# BMS_Rocket.net
KiCad netlist of a schematic drawn in Altium Designer
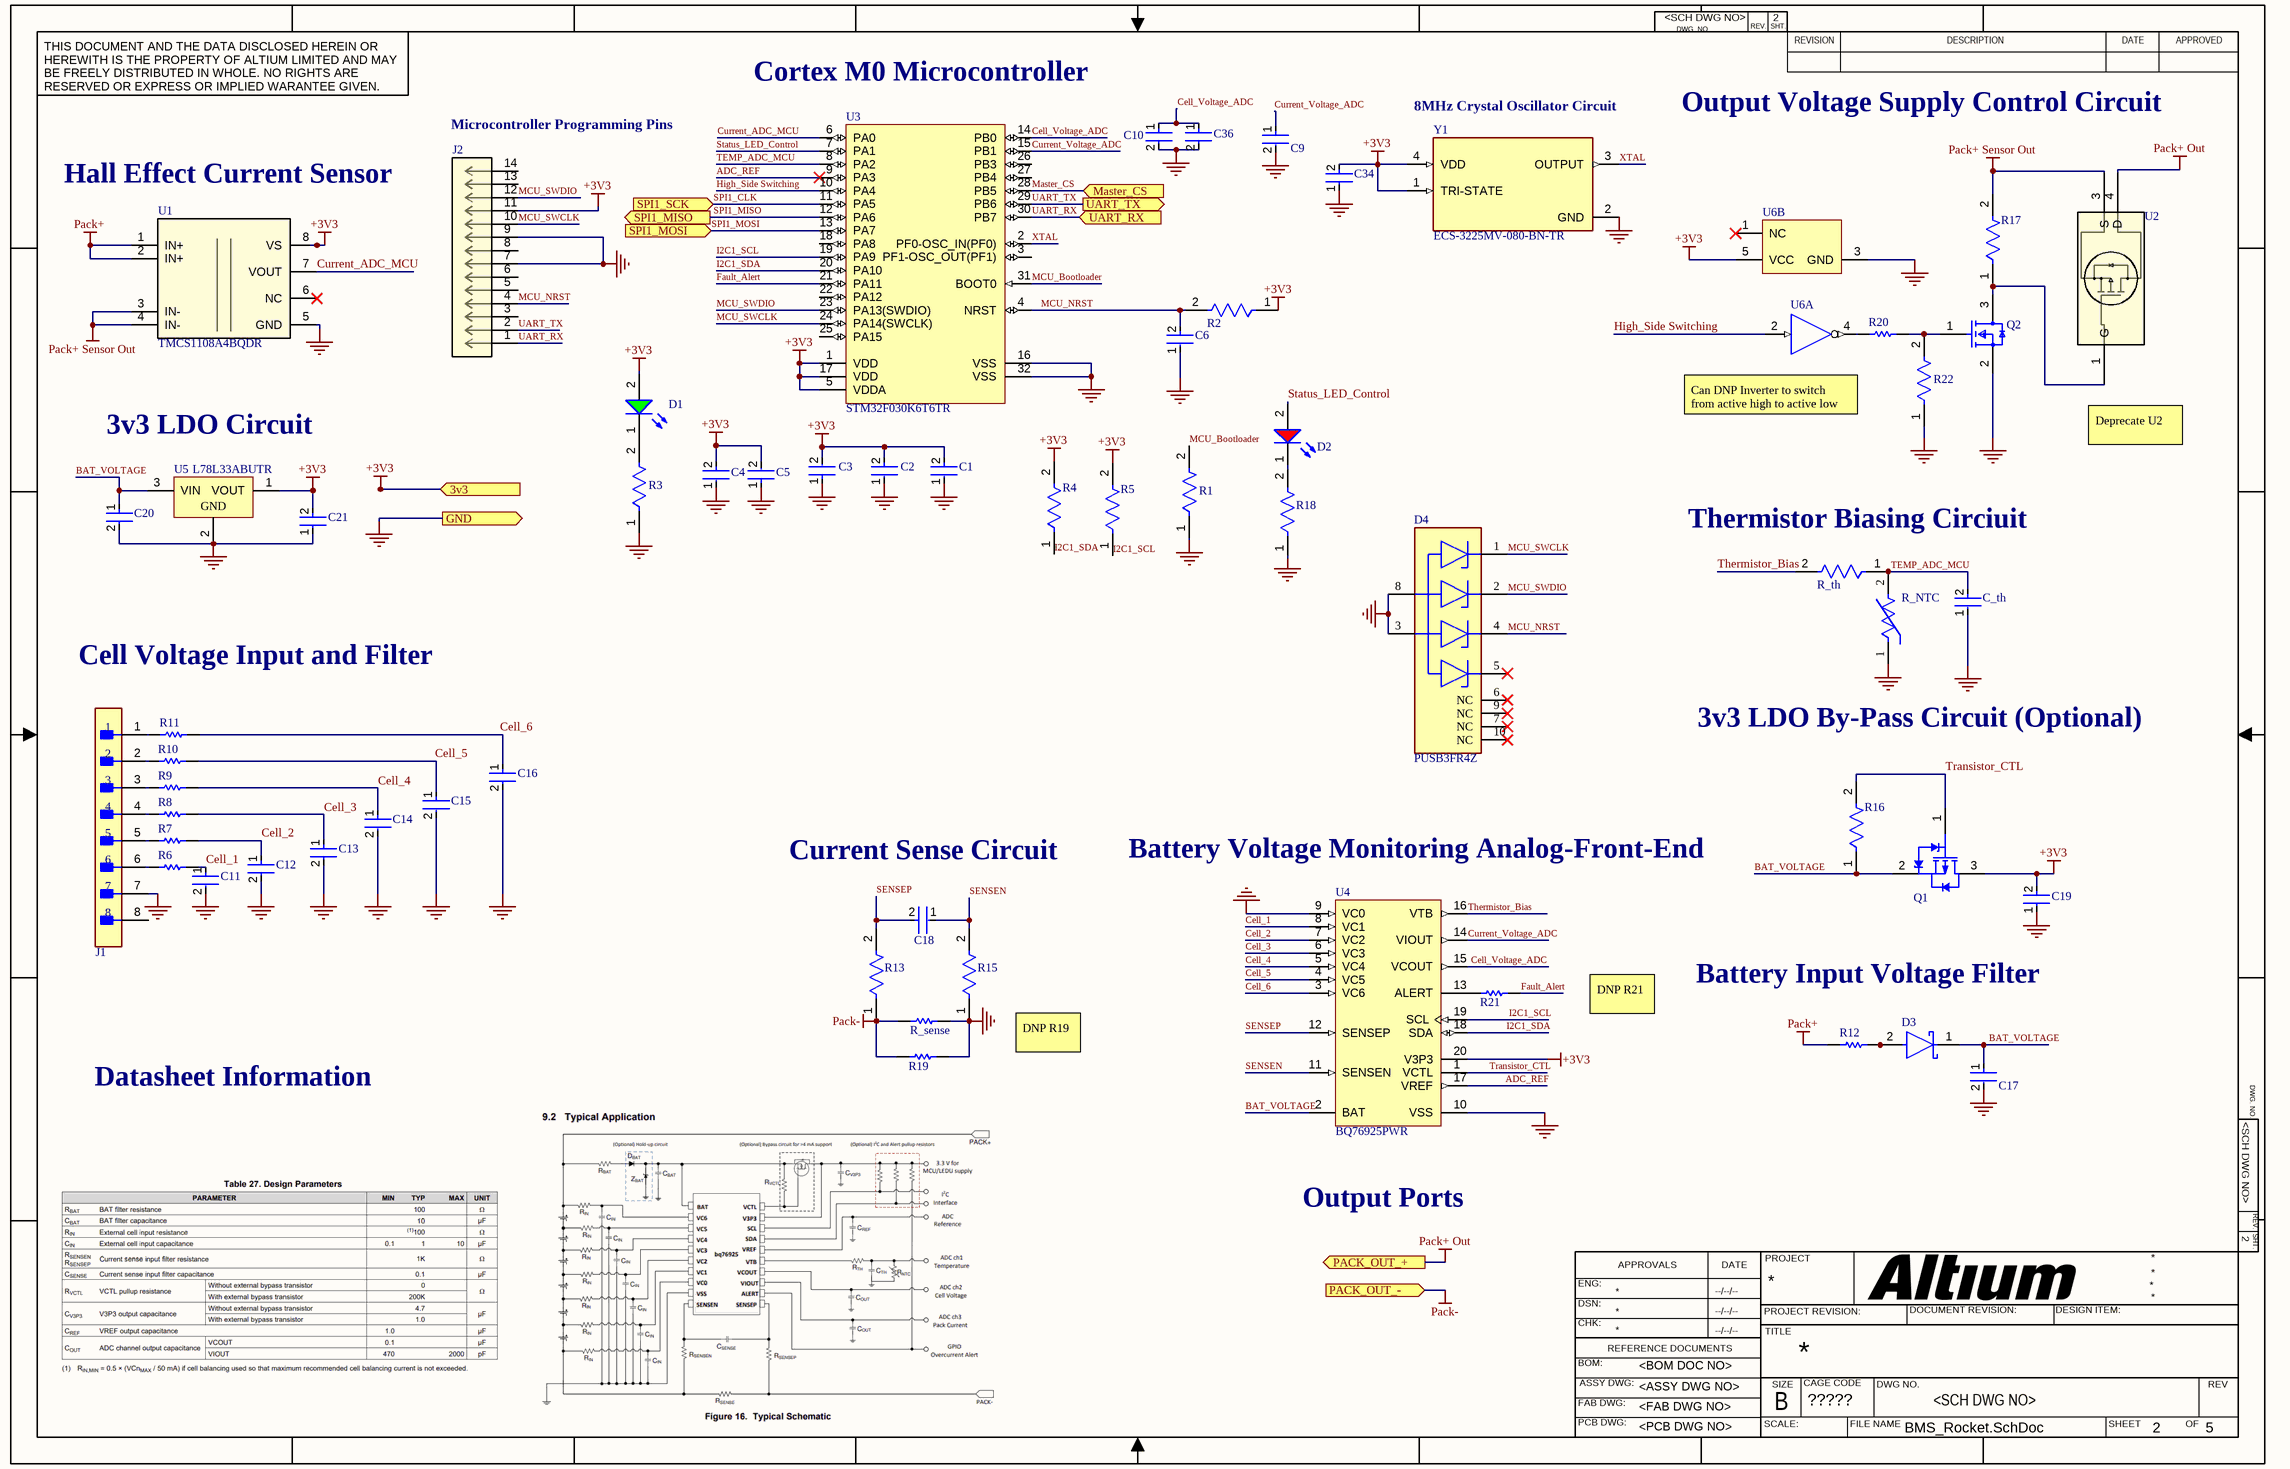
[diagram p0: BMS_Rocket.SchDoc]

(export (version "E")
  (design (tool "Eeschema 10.0.6"))
  (components
    (comp (ref "C1")
      (value "GRM155R71C104KA88D")
      (footprint "FP-GRM15-MFG")
      (description "CAP CER 0.1UF 16V X7R 0402")
      (fields
        (field (name "TOLERANCE") "10%")
        (field (name "OCTOPART") "https://octopart.com/grm155r71c104ka88d-murata-196880")
      )
      (libsource (lib "Altium Content Vault") (part "236180d848d6139a670b325ea6854c9"))
    )
    (comp (ref "C2")
      (value "GRM155R71C104KA88D")
      (footprint "FP-GRM15-MFG")
      (description "CAP CER 0.1UF 16V X7R 0402")
      (fields
        (field (name "TOLERANCE") "10%")
        (field (name "OCTOPART") "https://octopart.com/grm155r71c104ka88d-murata-196880")
      )
      (libsource (lib "Altium Content Vault") (part "236180d848d6139a670b325ea6854c9"))
    )
    (comp (ref "C3")
      (value "GRM188R6YA475KE15D")
      (footprint "FP-GRM188-0_2-IPC_C")
      (description "Chip Multilayer Ceramic Capacitors for General Purpose, 0603, 4.7uF, X5R, 15%, 10%, 35V")
      (fields (field (name "VOLTAGE") "35V") (field (name "TOLERANCE") "10%"))
      (libsource (lib "Altium Content Vault") (part "11868f565c42a9108669ba33697ecf6"))
    )
    (comp (ref "C4")
      (value "C1608X5R1H105K080AB")
      (footprint "FP-C1608-080-0_1-IPC_B")
      (description "Multilayer Ceramic Capacitors 1μF ±10% 50V X5R SMD 0603")
      (fields (field (name "VOLTAGE") "50V") (field (name "TOLERANCE") "10%"))
      (libsource (lib "Altium Content Vault") (part "236180d848d6139a670b325ea6854c9"))
    )
    (comp (ref "C5")
      (value "CC0603KRX7R9BB103")
      (footprint "FP-CC0603-DA-MFG")
      (description "CAP CER 10000PF 50V X7R 0603")
      (fields (field (name "TOLERANCE") "0.1") (field (name "MANUFACTURER") "YAGEO"))
      (libsource (lib "Altium Content Vault") (part "11868f565c42a9108669ba33697ecf6"))
    )
    (comp (ref "C6")
      (value "GRM155R71C104KA88D")
      (footprint "FP-GRM15-MFG")
      (description "CAP CER 0.1UF 16V X7R 0402")
      (fields
        (field (name "TOLERANCE") "10%")
        (field (name "OCTOPART") "https://octopart.com/grm155r71c104ka88d-murata-196880")
      )
      (libsource (lib "Altium Content Vault") (part "236180d848d6139a670b325ea6854c9"))
    )
    (comp (ref "C9")
      (value "GRM1885C1H202JA01D")
      (footprint "FP-GRM188-0_1-e0_2_0_5-IPC_B")
      (description "Chip Multilayer Ceramic Capacitors for General Purpose, 0603, 2000pF, C0G, 30ppm/°C, 5%, 50V")
      (fields (field (name "TOLERANCE") "5%") (field (name "VOLTAGE") "50V"))
      (libsource (lib "Altium Content Vault") (part "11868f565c42a9108669ba33697ecf6"))
    )
    (comp (ref "C10")
      (value "CC0402KRX7R8BB102")
      (footprint "FP-CC0402-MFG")
      (description "CAP CER 1000PF 25V X7R 0402")
      (fields
        (field (name "MANUFACTURER") "YAGEO")
        (field (name "OCTOPART") "https://octopart.com/cc0402krx7r8bb102-yageo-12885104")
      )
      (libsource (lib "Altium Content Vault") (part "11868f565c42a9108669ba33697ecf6"))
    )
    (comp (ref "C11")
      (value "UMK107AB7105KA-T")
      (footprint "FP-0603-L_1_6_0_15-W_0_8-IPC_C")
      (description "Ceramic Capacitor General Use 1uF ±10% 50V X7R 0603")
      (fields (field (name "TOLERANCE") "10%"))
      (libsource (lib "Altium Content Vault") (part "11868f565c42a9108669ba33697ecf6"))
    )
    (comp (ref "C12")
      (value "UMK107AB7105KA-T")
      (footprint "FP-0603-L_1_6_0_15-W_0_8-IPC_C")
      (description "Ceramic Capacitor General Use 1uF ±10% 50V X7R 0603")
      (fields (field (name "TOLERANCE") "10%"))
      (libsource (lib "Altium Content Vault") (part "11868f565c42a9108669ba33697ecf6"))
    )
    (comp (ref "C13")
      (value "UMK107AB7105KA-T")
      (footprint "FP-0603-L_1_6_0_15-W_0_8-IPC_C")
      (description "Ceramic Capacitor General Use 1uF ±10% 50V X7R 0603")
      (fields (field (name "TOLERANCE") "10%"))
      (libsource (lib "Altium Content Vault") (part "11868f565c42a9108669ba33697ecf6"))
    )
    (comp (ref "C14")
      (value "UMK107AB7105KA-T")
      (footprint "FP-0603-L_1_6_0_15-W_0_8-IPC_C")
      (description "Ceramic Capacitor General Use 1uF ±10% 50V X7R 0603")
      (fields (field (name "TOLERANCE") "10%"))
      (libsource (lib "Altium Content Vault") (part "11868f565c42a9108669ba33697ecf6"))
    )
    (comp (ref "C15")
      (value "UMK107AB7105KA-T")
      (footprint "FP-0603-L_1_6_0_15-W_0_8-IPC_C")
      (description "Ceramic Capacitor General Use 1uF ±10% 50V X7R 0603")
      (fields (field (name "TOLERANCE") "10%"))
      (libsource (lib "Altium Content Vault") (part "11868f565c42a9108669ba33697ecf6"))
    )
    (comp (ref "C16")
      (value "UMK107AB7105KA-T")
      (footprint "FP-0603-L_1_6_0_15-W_0_8-IPC_C")
      (description "Ceramic Capacitor General Use 1uF ±10% 50V X7R 0603")
      (fields (field (name "TOLERANCE") "10%"))
      (libsource (lib "Altium Content Vault") (part "11868f565c42a9108669ba33697ecf6"))
    )
    (comp (ref "C17")
      (value "C3216X5R1H106M160AB")
      (footprint "FP-C3216-160-0_2-MFG")
      (description "Multilayer Ceramic Capacitors 10uF ±20% 50V X5R SMD 1206")
      (fields (field (name "TOLERANCE") "20%"))
      (libsource (lib "Altium Content Vault") (part "11868f565c42a9108669ba33697ecf6"))
    )
    (comp (ref "C18")
      (value "GRM155R71C104KA88D")
      (footprint "FP-GRM15-MFG")
      (description "CAP CER 0.1UF 16V X7R 0402")
      (fields
        (field (name "TOLERANCE") "10%")
        (field (name "OCTOPART") "https://octopart.com/grm155r71c104ka88d-murata-196880")
      )
      (libsource (lib "Altium Content Vault") (part "236180d848d6139a670b325ea6854c9"))
    )
    (comp (ref "C19")
      (value "C1608X5R1H105K080AB")
      (footprint "FP-C1608-080-0_1-IPC_B")
      (description "Multilayer Ceramic Capacitors 1μF ±10% 50V X5R SMD 0603")
      (fields (field (name "VOLTAGE") "50V") (field (name "TOLERANCE") "10%"))
      (libsource (lib "Altium Content Vault") (part "236180d848d6139a670b325ea6854c9"))
    )
    (comp (ref "C20")
      (value "CGA3E3X7R1H334K080AB")
      (footprint "FP-CGA3E-0_3-0_1-IPC_B")
      (description "Cap Ceramic 330nF 50V X7R 10% Pad SMD 0603 +125°C Automotive T/R")
      (fields (field (name "TOLERANCE") "10%"))
      (libsource (lib "Altium Content Vault") (part "b4654b650e69147ec39a6b967a45e02"))
    )
    (comp (ref "C21")
      (value "GRM155R71C104KA88D")
      (footprint "FP-GRM15-MFG")
      (description "CAP CER 0.1UF 16V X7R 0402")
      (fields
        (field (name "TOLERANCE") "10%")
        (field (name "OCTOPART") "https://octopart.com/grm155r71c104ka88d-murata-196880")
      )
      (libsource (lib "Altium Content Vault") (part "236180d848d6139a670b325ea6854c9"))
    )
    (comp (ref "C34")
      (value "GRM155R71C104KA88D")
      (footprint "FP-GRM15-MFG")
      (description "CAP CER 0.1UF 16V X7R 0402")
      (fields
        (field (name "TOLERANCE") "10%")
        (field (name "OCTOPART") "https://octopart.com/grm155r71c104ka88d-murata-196880")
      )
      (libsource (lib "Altium Content Vault") (part "236180d848d6139a670b325ea6854c9"))
    )
    (comp (ref "C36")
      (value "CC0402KRX7R8BB102")
      (footprint "FP-CC0402-MFG")
      (description "CAP CER 1000PF 25V X7R 0402")
      (fields
        (field (name "MANUFACTURER") "YAGEO")
        (field (name "OCTOPART") "https://octopart.com/cc0402krx7r8bb102-yageo-12885104")
      )
      (libsource (lib "Altium Content Vault") (part "11868f565c42a9108669ba33697ecf6"))
    )
    (comp (ref "C_th")
      (value "GRM155R71C104KA88D")
      (footprint "FP-GRM15-MFG")
      (description "CAP CER 0.1UF 16V X7R 0402")
      (fields
        (field (name "TOLERANCE") "10%")
        (field (name "OCTOPART") "https://octopart.com/grm155r71c104ka88d-murata-196880")
      )
      (libsource (lib "Altium Content Vault") (part "236180d848d6139a670b325ea6854c9"))
    )
    (comp (ref "D1")
      (value "150060VS75000")
      (footprint "WL-SMCW_0603_150060xx75000")
      (description "WURTH ELEKTRONIK - 150060VS75000 - LED, Green, SMD, 0603, 30 mA, 2 V, 570 nm")
      (libsource (lib "Altium Content Vault") (part "LED_Green_2A-1K"))
    )
    (comp (ref "D2")
      (value "150060SS75000")
      (footprint "WL-SMCW_0603_150060xx75000")
      (description "Led, Red, 630 Nm, 1.9 V, 30 Ma, 60 Mcd Rohs Compliant: Yes")
      (libsource (lib "Altium Content Vault") (part "LED_Red_2A-1K"))
    )
    (comp (ref "D3")
      (value "B0520LW-7-F")
      (footprint "FP-SOD123-MFG")
      (description "DIODE SCHOTTKY 20V 500MA SOD123")
      (fields
        (field (name "OCTOPART") "https://octopart.com/b0520lw-7-f-diodes+inc.-325707")
        (field (name "MANUFACTURER") "Diodes Inc.")
      )
      (libsource (lib "Altium Content Vault") (part "1d6ec82d83fb6aee721767c19dac4b9"))
    )
    (comp (ref "D4")
      (value "PUSB3FR4Z")
      (footprint "FP-SOT1176-1-MFG")
      (description "TVS DIODE 3.3VWM 3VC DFN2510A-10")
      (libsource (lib "Altium Content Vault") (part "7af82cefb99888626757485c32e8fb9"))
    )
    (comp (ref "J1")
      (value "M20-9990846")
      (footprint "FP-M20-9990846-MFG")
      (description "CONN HEADER VERT 8POS 2.54MM")
      (libsource (lib "Altium Content Vault") (part "99ec2b232beb5d2356d4d77f6a047f0"))
    )
    (comp (ref "J2")
      (value "3220-14-0100-00")
      (footprint "CONN14_3220-14_CNC")
      (description "No Description Available")
      (libsource (lib "3220-14-0100-00") (part "3220-14-0100-00"))
    )
    (comp (ref "Q1")
      (value "BSS84AK,215")
      (footprint "NXP-SOT23_N")
      (description "P-Channel Trench MOSFET, -50 V, -0.18 A, -55 to 150 degC, 3-Pin SOT23, Tape and Reel")
      (fields (field (name "MANUFACTURER") "NXP Semiconductors"))
      (libsource (lib "Altium Content Vault") (part "NXP-PMOS-GSD-3_B"))
    )
    (comp (ref "Q2")
      (value "2N7002-7-F")
      (footprint "FP-SOT23-MFG")
      (description "MOSFET N-CH 60V 115MA SOT23-3")
      (fields (field (name "VOLTAGE") "60V"))
      (libsource (lib "Altium Content Vault") (part "3b9c635fedb024a5347a57b145af9cc"))
    )
    (comp (ref "R1")
      (value "RC0603FR-0710KL")
      (footprint "FP-RC0603-0_55-IPC_C")
      (description "RES 10K OHM 1% 1/10W 0603")
      (fields (field (name "TOLERANCE") "1%"))
      (libsource (lib "Altium Content Vault") (part "1029c3af85768c4190bb7ad29bc67b5"))
    )
    (comp (ref "R2")
      (value "RC0603FR-0710KL")
      (footprint "FP-RC0603-0_55-IPC_C")
      (description "RES 10K OHM 1% 1/10W 0603")
      (fields (field (name "TOLERANCE") "1%"))
      (libsource (lib "Altium Content Vault") (part "1029c3af85768c4190bb7ad29bc67b5"))
    )
    (comp (ref "R3")
      (value "RC0603FR-0710KL")
      (footprint "FP-RC0603-0_55-IPC_C")
      (description "RES 10K OHM 1% 1/10W 0603")
      (fields (field (name "TOLERANCE") "1%"))
      (libsource (lib "Altium Content Vault") (part "1029c3af85768c4190bb7ad29bc67b5"))
    )
    (comp (ref "R4")
      (value "CRCW06034K70FKEA")
      (footprint "FP-CRCW0603-e3-IPC_A")
      (description "RES Thick Film, 4.7kΩ, 1%, 0.1W, 100ppm/°C, 0603")
      (fields (field (name "TOLERANCE") "1%"))
      (libsource (lib "Altium Content Vault") (part "1029c3af85768c4190bb7ad29bc67b5"))
    )
    (comp (ref "R5")
      (value "CRCW06034K70FKEA")
      (footprint "FP-CRCW0603-e3-IPC_A")
      (description "RES Thick Film, 4.7kΩ, 1%, 0.1W, 100ppm/°C, 0603")
      (fields (field (name "TOLERANCE") "1%"))
      (libsource (lib "Altium Content Vault") (part "1029c3af85768c4190bb7ad29bc67b5"))
    )
    (comp (ref "R6")
      (value "CRCW0603100RFKEA")
      (footprint "RESC1609X50X30ML8T20")
      (description "Chip Resistor, 100 Ohm, +/- 1%, 100 mW,-55 to 155 degC, 0603 (1608 Metric), RoHS, Tape and Ree")
      (fields (field (name "MANUFACTURER") "Vishay Semiconductor"))
      (libsource (lib "Altium Content Vault") (part "RES-2"))
    )
    (comp (ref "R7")
      (value "CRCW0603100RFKEA")
      (footprint "RESC1609X50X30ML8T20")
      (description "Chip Resistor, 100 Ohm, +/- 1%, 100 mW,-55 to 155 degC, 0603 (1608 Metric), RoHS, Tape and Ree")
      (fields (field (name "MANUFACTURER") "Vishay Semiconductor"))
      (libsource (lib "Altium Content Vault") (part "RES-2"))
    )
    (comp (ref "R8")
      (value "CRCW0603100RFKEA")
      (footprint "RESC1609X50X30ML8T20")
      (description "Chip Resistor, 100 Ohm, +/- 1%, 100 mW,-55 to 155 degC, 0603 (1608 Metric), RoHS, Tape and Ree")
      (fields (field (name "MANUFACTURER") "Vishay Semiconductor"))
      (libsource (lib "Altium Content Vault") (part "RES-2"))
    )
    (comp (ref "R9")
      (value "CRCW0603100RFKEA")
      (footprint "RESC1609X50X30ML8T20")
      (description "Chip Resistor, 100 Ohm, +/- 1%, 100 mW,-55 to 155 degC, 0603 (1608 Metric), RoHS, Tape and Ree")
      (fields (field (name "MANUFACTURER") "Vishay Semiconductor"))
      (libsource (lib "Altium Content Vault") (part "RES-2"))
    )
    (comp (ref "R10")
      (value "CRCW0603100RFKEA")
      (footprint "RESC1609X50X30ML8T20")
      (description "Chip Resistor, 100 Ohm, +/- 1%, 100 mW,-55 to 155 degC, 0603 (1608 Metric), RoHS, Tape and Ree")
      (fields (field (name "MANUFACTURER") "Vishay Semiconductor"))
      (libsource (lib "Altium Content Vault") (part "RES-2"))
    )
    (comp (ref "R11")
      (value "CRCW0603100RFKEA")
      (footprint "RESC1609X50X30ML8T20")
      (description "Chip Resistor, 100 Ohm, +/- 1%, 100 mW,-55 to 155 degC, 0603 (1608 Metric), RoHS, Tape and Ree")
      (fields (field (name "MANUFACTURER") "Vishay Semiconductor"))
      (libsource (lib "Altium Content Vault") (part "RES-2"))
    )
    (comp (ref "R12")
      (value "RK73B1JTTD111J")
      (footprint "RESC1608X55X30NL20T10")
      (fields (field (name "MANUFACTURER") "KOA Speer"))
      (libsource (lib "Altium Content Vault") (part "RES"))
    )
    (comp (ref "R13")
      (value "AC0603FR-071KL")
      (footprint "FP-AC0603-IPC_B")
      (description "RES 1kΩ 1.00% 0.1W 0603")
      (fields (field (name "TOLERANCE") "1%"))
      (libsource (lib "Altium Content Vault") (part "1029c3af85768c4190bb7ad29bc67b5"))
    )
    (comp (ref "R15")
      (value "AC0603FR-071KL")
      (footprint "FP-AC0603-IPC_B")
      (description "RES 1kΩ 1.00% 0.1W 0603")
      (fields (field (name "TOLERANCE") "1%"))
      (libsource (lib "Altium Content Vault") (part "1029c3af85768c4190bb7ad29bc67b5"))
    )
    (comp (ref "R16")
      (value "CRCW0603200KFKEA")
      (footprint "FP-CRCW0603-e3-IPC_C")
      (description "RES Thick Film, 200kΩ, 1%, 0.1W, 100ppm/°C, 0603")
      (fields (field (name "TOLERANCE") "1%"))
      (libsource (lib "Altium Content Vault") (part "1029c3af85768c4190bb7ad29bc67b5"))
    )
    (comp (ref "R17")
      (value "CRCW0603200KFKEA")
      (footprint "FP-CRCW0603-e3-IPC_C")
      (description "RES Thick Film, 200kΩ, 1%, 0.1W, 100ppm/°C, 0603")
      (fields (field (name "TOLERANCE") "1%"))
      (libsource (lib "Altium Content Vault") (part "1029c3af85768c4190bb7ad29bc67b5"))
    )
    (comp (ref "R18")
      (value "RC0603FR-0710KL")
      (footprint "FP-RC0603-0_55-IPC_C")
      (description "RES 10K OHM 1% 1/10W 0603")
      (fields (field (name "TOLERANCE") "1%"))
      (libsource (lib "Altium Content Vault") (part "1029c3af85768c4190bb7ad29bc67b5"))
    )
    (comp (ref "R19")
      (value "RC0603JR-070RL")
      (footprint "RESC1608X55X25ML10T15")
      (description "Chip Resistor, 0 Ohm, +/- 5%, 0.1 W, -55 to 155 degC, 0603 (1608 Metric), RoHS, Tape and Reel")
      (fields (field (name "TOLERANCE") "5%") (field (name "MANUFACTURER") "Yageo"))
      (libsource (lib "Altium Content Vault") (part "RES-2"))
    )
    (comp (ref "R20")
      (value "RK73B1JTTD111J")
      (footprint "RESC1608X55X30NL20T10")
      (fields (field (name "MANUFACTURER") "KOA Speer"))
      (libsource (lib "Altium Content Vault") (part "RES"))
    )
    (comp (ref "R21")
      (value "RC0603JR-070RL")
      (footprint "RESC1608X55X25ML10T15")
      (description "Chip Resistor, 0 Ohm, +/- 5%, 0.1 W, -55 to 155 degC, 0603 (1608 Metric), RoHS, Tape and Reel")
      (fields (field (name "TOLERANCE") "5%") (field (name "MANUFACTURER") "Yageo"))
      (libsource (lib "Altium Content Vault") (part "RES-2"))
    )
    (comp (ref "R22")
      (value "RC0603FR-0710KL")
      (footprint "FP-RC0603-0_55-IPC_C")
      (description "RES 10K OHM 1% 1/10W 0603")
      (fields (field (name "TOLERANCE") "1%"))
      (libsource (lib "Altium Content Vault") (part "1029c3af85768c4190bb7ad29bc67b5"))
    )
    (comp (ref "R_NTC")
      (value "ERT-J1VG103FA")
      (footprint "FP-ERTJ1-MFG")
      (description "THERMISTOR NTC 10KOHM 3380K 0603")
      (fields (field (name "TOLERANCE") "1%"))
      (libsource (lib "Altium Content Vault") (part "3b148a6ebabc5fb4d708a66c052d352"))
    )
    (comp (ref "R_sense")
      (value "RL1220S-R15-F")
      (footprint "RESC2013X50X40LL20T20")
      (fields (field (name "MANUFACTURER") "Susumu"))
      (libsource (lib "Altium Content Vault") (part "RES"))
    )
    (comp (ref "R_th")
      (value "RC0603FR-0710KL")
      (footprint "FP-RC0603-0_55-IPC_C")
      (description "RES 10K OHM 1% 1/10W 0603")
      (fields (field (name "TOLERANCE") "1%"))
      (libsource (lib "Altium Content Vault") (part "1029c3af85768c4190bb7ad29bc67b5"))
    )
    (comp (ref "U1")
      (value "TMCS1108A4BQDR")
      (footprint "D0008A-IPC_A")
      (description "No Description Available")
      (libsource (lib "TMCS1108A4BQDR") (part "TMCS1108A4BQDR"))
    )
    (comp (ref "U2")
      (value "FQD11P06TM")
      (footprint "TO-252-3_ONS")
      (description "No Description Available")
      (libsource (lib "FQD11P06TM") (part "FQD11P06TM"))
    )
    (comp (ref "U3")
      (value "STM32F030K6T6TR")
      (footprint "STM-LQFP32_M")
      (fields (field (name "MANUFACTURER") "STMicroelectronics"))
      (libsource (lib "Altium Content Vault") (part "MC-ARM-STM32F030-LQFP32"))
    )
    (comp (ref "U4")
      (value "BQ76925PWR")
      (footprint "PW0020A_L")
      (fields (field (name "MANUFACTURER") "Texas Instruments"))
      (libsource (lib "Altium Content Vault") (part "TI-BQ76925PW20"))
    )
    (comp (ref "U5")
      (value "L78L33ABUTR")
      (footprint "SOT-89_N")
      (description "Positive Voltage Regulator, 3.3V, 4-Pin SOT-89, Tape and Reel")
      (libsource (lib "Altium Content Vault") (part "PM-REG-7805-SIL3"))
    )
    (comp (ref "U6")
      (value "SN74LVC1G04DCKR")
      (footprint "DCK0005A_N")
      (description "Single Inverter, DCK0005A, LARGE T&R")
      (fields
        (field (name "GENERIC PART NUMBER") "SN74LVC1G04")
        (field (name "MANUFACTURER") "Texas Instruments")
      )
      (libsource (lib "Altium Content Vault") (part "TI-SN74XXX1XX4-XX-5"))
    )
    (comp (ref "Y1")
      (value "ECS-3225MV-080-BN-TR")
      (footprint "OSC_ECS-3225MV-080-BN-TR")
      (description "8 MHz XO (Standard) HCMOS Oscillator 1.62V ~ 3.63V Enable/Disable 4-SMD, No Lead")
      (fields (field (name "MF") "ECS Inc."))
      (libsource (lib "ECS-3225MV-080-BN-TR") (part "ECS-3225MV-080-BN-TR"))
    )
  )
  (nets
    (net (code "1") (name "+3V3") (class "Default")
      (node (ref "C1") (pin "2") (pinfunction "2_2") (pintype "passive"))
      (node (ref "C19") (pin "2") (pinfunction "2_2") (pintype "passive"))
      (node (ref "C2") (pin "2") (pinfunction "2_2") (pintype "passive"))
      (node (ref "C21") (pin "2") (pinfunction "2_2") (pintype "passive"))
      (node (ref "C3") (pin "2") (pinfunction "2_2") (pintype "passive"))
      (node (ref "C34") (pin "2") (pinfunction "2_2") (pintype "passive"))
      (node (ref "C4") (pin "2") (pinfunction "2_2") (pintype "passive"))
      (node (ref "C5") (pin "2") (pinfunction "2_2") (pintype "passive"))
      (node (ref "D1") (pin "2") (pinfunction "A_2") (pintype "passive"))
      (node (ref "J2") (pin "11") (pinfunction "11_11") (pintype "passive"))
      (node (ref "Q1") (pin "3") (pinfunction "D_3") (pintype "passive"))
      (node (ref "R2") (pin "1") (pinfunction "1_1") (pintype "passive"))
      (node (ref "R4") (pin "2") (pinfunction "2_2") (pintype "passive"))
      (node (ref "R5") (pin "2") (pinfunction "2_2") (pintype "passive"))
      (node (ref "U1") (pin "8") (pinfunction "VS_8") (pintype "power_in"))
      (node (ref "U3") (pin "1") (pinfunction "VDD_1") (pintype "power_in"))
      (node (ref "U3") (pin "17") (pinfunction "VDD_17") (pintype "power_in"))
      (node (ref "U3") (pin "5") (pinfunction "VDDA_5") (pintype "power_in"))
      (node (ref "U4") (pin "20") (pinfunction "V3P3_20") (pintype "power_in"))
      (node (ref "U5") (pin "1") (pinfunction "VOUT_1") (pintype "power_in"))
      (node (ref "U6") (pin "5") (pinfunction "VCC_5") (pintype "power_in"))
      (node (ref "Y1") (pin "1") (pinfunction "TRI-STATE_1") (pintype "input"))
      (node (ref "Y1") (pin "4") (pinfunction "VDD_4") (pintype "input"))
    )
    (net (code "2") (name "/ADC_REF") (class "Default")
      (node (ref "U3") (pin "9") (pinfunction "PA3_9") (pintype "bidirectional"))
      (node (ref "U4") (pin "17") (pinfunction "VREF_17") (pintype "output"))
    )
    (net (code "3") (name "/BAT_VOLTAGE") (class "Default")
      (node (ref "C17") (pin "1") (pinfunction "1_1") (pintype "passive"))
      (node (ref "C20") (pin "1") (pinfunction "1_1") (pintype "passive"))
      (node (ref "D3") (pin "1") (pinfunction "C_1") (pintype "passive"))
      (node (ref "Q1") (pin "2") (pinfunction "S_2") (pintype "passive"))
      (node (ref "R16") (pin "1") (pinfunction "1_1") (pintype "passive"))
      (node (ref "U4") (pin "2") (pinfunction "BAT_2") (pintype "power_in"))
      (node (ref "U5") (pin "3") (pinfunction "VIN_3") (pintype "power_in"))
    )
    (net (code "4") (name "/Cell_1") (class "Default")
      (node (ref "C11") (pin "1") (pinfunction "1_1") (pintype "passive"))
      (node (ref "R6") (pin "2") (pinfunction "2_2") (pintype "passive"))
      (node (ref "U4") (pin "8") (pinfunction "VC1_8") (pintype "input"))
    )
    (net (code "5") (name "/Cell_2") (class "Default")
      (node (ref "C12") (pin "1") (pinfunction "1_1") (pintype "passive"))
      (node (ref "R7") (pin "2") (pinfunction "2_2") (pintype "passive"))
      (node (ref "U4") (pin "7") (pinfunction "VC2_7") (pintype "input"))
    )
    (net (code "6") (name "/Cell_3") (class "Default")
      (node (ref "C13") (pin "1") (pinfunction "1_1") (pintype "passive"))
      (node (ref "R8") (pin "2") (pinfunction "2_2") (pintype "passive"))
      (node (ref "U4") (pin "6") (pinfunction "VC3_6") (pintype "input"))
    )
    (net (code "7") (name "/Cell_4") (class "Default")
      (node (ref "C14") (pin "1") (pinfunction "1_1") (pintype "passive"))
      (node (ref "R9") (pin "2") (pinfunction "2_2") (pintype "passive"))
      (node (ref "U4") (pin "5") (pinfunction "VC4_5") (pintype "input"))
    )
    (net (code "8") (name "/Cell_5") (class "Default")
      (node (ref "C15") (pin "1") (pinfunction "1_1") (pintype "passive"))
      (node (ref "R10") (pin "2") (pinfunction "2_2") (pintype "passive"))
      (node (ref "U4") (pin "4") (pinfunction "VC5_4") (pintype "input"))
    )
    (net (code "9") (name "/Cell_6") (class "Default")
      (node (ref "C16") (pin "1") (pinfunction "1_1") (pintype "passive"))
      (node (ref "R11") (pin "2") (pinfunction "2_2") (pintype "passive"))
      (node (ref "U4") (pin "3") (pinfunction "VC6_3") (pintype "input"))
    )
    (net (code "10") (name "/Cell_Voltage_ADC") (class "Default")
      (node (ref "C10") (pin "1") (pinfunction "1_1") (pintype "passive"))
      (node (ref "C36") (pin "1") (pinfunction "1_1") (pintype "passive"))
      (node (ref "U3") (pin "14") (pinfunction "PB0_14") (pintype "bidirectional"))
      (node (ref "U4") (pin "15") (pinfunction "VCOUT_15") (pintype "output"))
    )
    (net (code "11") (name "/Current_ADC_MCU") (class "Default")
      (node (ref "U1") (pin "7") (pinfunction "VOUT_7") (pintype "passive"))
      (node (ref "U3") (pin "6") (pinfunction "PA0_6") (pintype "bidirectional"))
    )
    (net (code "12") (name "/Current_Voltage_ADC") (class "Default")
      (node (ref "C9") (pin "1") (pinfunction "1_1") (pintype "passive"))
      (node (ref "U3") (pin "15") (pinfunction "PB1_15") (pintype "bidirectional"))
      (node (ref "U4") (pin "14") (pinfunction "VIOUT_14") (pintype "output"))
    )
    (net (code "13") (name "/Fault_Alert") (class "Default")
      (node (ref "R21") (pin "1") (pinfunction "1_1") (pintype "passive"))
      (node (ref "U3") (pin "21") (pinfunction "PA11_21") (pintype "bidirectional"))
    )
    (net (code "14") (name "/High_Side Switching") (class "Default")
      (node (ref "U3") (pin "10") (pinfunction "PA4_10") (pintype "bidirectional"))
      (node (ref "U6") (pin "2") (pinfunction "A_2") (pintype "input"))
    )
    (net (code "15") (name "/I2C1_SCL") (class "Default")
      (node (ref "R5") (pin "1") (pinfunction "1_1") (pintype "passive"))
      (node (ref "U3") (pin "19") (pinfunction "PA9_19") (pintype "bidirectional"))
      (node (ref "U4") (pin "19") (pinfunction "SCL_19") (pintype "input"))
    )
    (net (code "16") (name "/I2C1_SDA") (class "Default")
      (node (ref "R4") (pin "1") (pinfunction "1_1") (pintype "passive"))
      (node (ref "U3") (pin "20") (pinfunction "PA10_20") (pintype "bidirectional"))
      (node (ref "U4") (pin "18") (pinfunction "SDA_18") (pintype "bidirectional"))
    )
    (net (code "17") (name "/MCU_Bootloader") (class "Default")
      (node (ref "R1") (pin "2") (pinfunction "2_2") (pintype "passive"))
      (node (ref "U3") (pin "31") (pinfunction "BOOT0_31") (pintype "input"))
    )
    (net (code "18") (name "/MCU_NRST") (class "Default")
      (node (ref "C6") (pin "2") (pinfunction "2_2") (pintype "passive"))
      (node (ref "D4") (pin "4") (pinfunction "CH3_4") (pintype "passive"))
      (node (ref "J2") (pin "4") (pinfunction "4_4") (pintype "passive"))
      (node (ref "R2") (pin "2") (pinfunction "2_2") (pintype "passive"))
      (node (ref "U3") (pin "4") (pinfunction "NRST_4") (pintype "bidirectional"))
    )
    (net (code "19") (name "/MCU_SWCLK") (class "Default")
      (node (ref "D4") (pin "1") (pinfunction "CH1_1") (pintype "passive"))
      (node (ref "J2") (pin "10") (pinfunction "10_10") (pintype "passive"))
      (node (ref "U3") (pin "24") (pinfunction "PA14(SWCLK)_24") (pintype "bidirectional"))
    )
    (net (code "20") (name "/MCU_SWDIO") (class "Default")
      (node (ref "D4") (pin "2") (pinfunction "CH2_2") (pintype "passive"))
      (node (ref "J2") (pin "12") (pinfunction "12_12") (pintype "passive"))
      (node (ref "U3") (pin "23") (pinfunction "PA13(SWDIO)_23") (pintype "bidirectional"))
    )
    (net (code "21") (name "/Master_CS") (class "Default")
      (node (ref "U3") (pin "28") (pinfunction "PB5_28") (pintype "bidirectional"))
    )
    (net (code "22") (name "/SENSEN") (class "Default")
      (node (ref "C18") (pin "1") (pinfunction "1_1") (pintype "passive"))
      (node (ref "R15") (pin "2") (pinfunction "2_2") (pintype "passive"))
      (node (ref "U4") (pin "11") (pinfunction "SENSEN_11") (pintype "input"))
    )
    (net (code "23") (name "/SENSEP") (class "Default")
      (node (ref "C18") (pin "2") (pinfunction "2_2") (pintype "passive"))
      (node (ref "R13") (pin "2") (pinfunction "2_2") (pintype "passive"))
      (node (ref "U4") (pin "12") (pinfunction "SENSEP_12") (pintype "input"))
    )
    (net (code "24") (name "/SPI1_CLK") (class "Default")
      (node (ref "U3") (pin "11") (pinfunction "PA5_11") (pintype "bidirectional"))
    )
    (net (code "25") (name "/SPI1_MISO") (class "Default")
      (node (ref "U3") (pin "12") (pinfunction "PA6_12") (pintype "bidirectional"))
    )
    (net (code "26") (name "/SPI1_MOSI") (class "Default")
      (node (ref "U3") (pin "13") (pinfunction "PA7_13") (pintype "bidirectional"))
    )
    (net (code "27") (name "/Status_LED_Control") (class "Default")
      (node (ref "D2") (pin "2") (pinfunction "A_2") (pintype "passive"))
      (node (ref "U3") (pin "7") (pinfunction "PA1_7") (pintype "bidirectional"))
    )
    (net (code "28") (name "/TEMP_ADC_MCU") (class "Default")
      (node (ref "C_th") (pin "2") (pinfunction "2_2") (pintype "passive"))
      (node (ref "R_NTC") (pin "2") (pinfunction "2_2") (pintype "passive"))
      (node (ref "R_th") (pin "1") (pinfunction "1_1") (pintype "passive"))
      (node (ref "U3") (pin "8") (pinfunction "PA2_8") (pintype "bidirectional"))
    )
    (net (code "29") (name "/Thermistor_Bias") (class "Default")
      (node (ref "R_th") (pin "2") (pinfunction "2_2") (pintype "passive"))
      (node (ref "U4") (pin "16") (pinfunction "VTB_16") (pintype "output"))
    )
    (net (code "30") (name "/Transistor_CTL") (class "Default")
      (node (ref "Q1") (pin "1") (pinfunction "G_1") (pintype "passive"))
      (node (ref "R16") (pin "2") (pinfunction "2_2") (pintype "passive"))
      (node (ref "U4") (pin "1") (pinfunction "VCTL_1") (pintype "power_in"))
    )
    (net (code "31") (name "/UART_RX") (class "Default")
      (node (ref "J2") (pin "1") (pinfunction "1_1") (pintype "passive"))
      (node (ref "U3") (pin "30") (pinfunction "PB7_30") (pintype "bidirectional"))
    )
    (net (code "32") (name "/UART_TX") (class "Default")
      (node (ref "J2") (pin "2") (pinfunction "2_2") (pintype "passive"))
      (node (ref "U3") (pin "29") (pinfunction "PB6_29") (pintype "bidirectional"))
    )
    (net (code "33") (name "/XTAL") (class "Default")
      (node (ref "U3") (pin "2") (pinfunction "PF0-OSC_IN(PF0)_2") (pintype "bidirectional"))
      (node (ref "Y1") (pin "3") (pinfunction "OUTPUT_3") (pintype "output"))
    )
    (net (code "34") (name "GND") (class "Default")
      (node (ref "C1") (pin "1") (pinfunction "1_1") (pintype "passive"))
      (node (ref "C10") (pin "2") (pinfunction "2_2") (pintype "passive"))
      (node (ref "C11") (pin "2") (pinfunction "2_2") (pintype "passive"))
      (node (ref "C12") (pin "2") (pinfunction "2_2") (pintype "passive"))
      (node (ref "C13") (pin "2") (pinfunction "2_2") (pintype "passive"))
      (node (ref "C14") (pin "2") (pinfunction "2_2") (pintype "passive"))
      (node (ref "C15") (pin "2") (pinfunction "2_2") (pintype "passive"))
      (node (ref "C16") (pin "2") (pinfunction "2_2") (pintype "passive"))
      (node (ref "C17") (pin "2") (pinfunction "2_2") (pintype "passive"))
      (node (ref "C19") (pin "1") (pinfunction "1_1") (pintype "passive"))
      (node (ref "C2") (pin "1") (pinfunction "1_1") (pintype "passive"))
      (node (ref "C20") (pin "2") (pinfunction "2_2") (pintype "passive"))
      (node (ref "C21") (pin "1") (pinfunction "1_1") (pintype "passive"))
      (node (ref "C3") (pin "1") (pinfunction "1_1") (pintype "passive"))
      (node (ref "C34") (pin "1") (pinfunction "1_1") (pintype "passive"))
      (node (ref "C36") (pin "2") (pinfunction "2_2") (pintype "passive"))
      (node (ref "C4") (pin "1") (pinfunction "1_1") (pintype "passive"))
      (node (ref "C5") (pin "1") (pinfunction "1_1") (pintype "passive"))
      (node (ref "C6") (pin "1") (pinfunction "1_1") (pintype "passive"))
      (node (ref "C9") (pin "2") (pinfunction "2_2") (pintype "passive"))
      (node (ref "C_th") (pin "1") (pinfunction "1_1") (pintype "passive"))
      (node (ref "D4") (pin "3") (pinfunction "GND_3") (pintype "power_in"))
      (node (ref "D4") (pin "8") (pinfunction "GND_8") (pintype "power_in"))
      (node (ref "J1") (pin "7") (pinfunction "7_7") (pintype "passive"))
      (node (ref "J2") (pin "7") (pinfunction "7_7") (pintype "passive"))
      (node (ref "J2") (pin "9") (pinfunction "9_9") (pintype "passive"))
      (node (ref "Q2") (pin "2") (pinfunction "S_2") (pintype "passive"))
      (node (ref "R1") (pin "1") (pinfunction "1_1") (pintype "passive"))
      (node (ref "R15") (pin "1") (pinfunction "1_1") (pintype "passive"))
      (node (ref "R18") (pin "1") (pinfunction "1_1") (pintype "passive"))
      (node (ref "R19") (pin "1") (pinfunction "1_1") (pintype "passive"))
      (node (ref "R22") (pin "1") (pinfunction "1_1") (pintype "passive"))
      (node (ref "R3") (pin "1") (pinfunction "1_1") (pintype "passive"))
      (node (ref "R_NTC") (pin "1") (pinfunction "1_1") (pintype "passive"))
      (node (ref "R_sense") (pin "1") (pinfunction "1_1") (pintype "passive"))
      (node (ref "U1") (pin "5") (pinfunction "GND_5") (pintype "power_in"))
      (node (ref "U3") (pin "16") (pinfunction "VSS_16") (pintype "power_in"))
      (node (ref "U3") (pin "32") (pinfunction "VSS_32") (pintype "power_in"))
      (node (ref "U4") (pin "10") (pinfunction "VSS_10") (pintype "power_in"))
      (node (ref "U4") (pin "9") (pinfunction "VC0_9") (pintype "input"))
      (node (ref "U5") (pin "2") (pinfunction "GND_2") (pintype "power_in"))
      (node (ref "U6") (pin "3") (pinfunction "GND_3") (pintype "power_in"))
      (node (ref "Y1") (pin "2") (pinfunction "GND_2") (pintype "power_in"))
    )
    (net (code "35") (name "Net-(D1-K)") (class "Default")
      (node (ref "D1") (pin "1") (pinfunction "K_1") (pintype "passive"))
      (node (ref "R3") (pin "2") (pinfunction "2_2") (pintype "passive"))
    )
    (net (code "36") (name "Net-(D2-K)") (class "Default")
      (node (ref "D2") (pin "1") (pinfunction "K_1") (pintype "passive"))
      (node (ref "R18") (pin "2") (pinfunction "2_2") (pintype "passive"))
    )
    (net (code "37") (name "Net-(D3-A)") (class "Default")
      (node (ref "D3") (pin "2") (pinfunction "A_2") (pintype "passive"))
      (node (ref "R12") (pin "2") (pinfunction "2_2") (pintype "passive"))
    )
    (net (code "38") (name "Net-(J1-Pad1)") (class "Default")
      (node (ref "J1") (pin "1") (pinfunction "1_1") (pintype "passive"))
      (node (ref "R11") (pin "1") (pinfunction "1_1") (pintype "passive"))
    )
    (net (code "39") (name "Net-(J1-Pad2)") (class "Default")
      (node (ref "J1") (pin "2") (pinfunction "2_2") (pintype "passive"))
      (node (ref "R10") (pin "1") (pinfunction "1_1") (pintype "passive"))
    )
    (net (code "40") (name "Net-(J1-Pad3)") (class "Default")
      (node (ref "J1") (pin "3") (pinfunction "3_3") (pintype "passive"))
      (node (ref "R9") (pin "1") (pinfunction "1_1") (pintype "passive"))
    )
    (net (code "41") (name "Net-(J1-Pad4)") (class "Default")
      (node (ref "J1") (pin "4") (pinfunction "4_4") (pintype "passive"))
      (node (ref "R8") (pin "1") (pinfunction "1_1") (pintype "passive"))
    )
    (net (code "42") (name "Net-(J1-Pad5)") (class "Default")
      (node (ref "J1") (pin "5") (pinfunction "5_5") (pintype "passive"))
      (node (ref "R7") (pin "1") (pinfunction "1_1") (pintype "passive"))
    )
    (net (code "43") (name "Net-(J1-Pad6)") (class "Default")
      (node (ref "J1") (pin "6") (pinfunction "6_6") (pintype "passive"))
      (node (ref "R6") (pin "1") (pinfunction "1_1") (pintype "passive"))
    )
    (net (code "44") (name "Net-(Q2-D)") (class "Default")
      (node (ref "Q2") (pin "3") (pinfunction "D_3") (pintype "passive"))
      (node (ref "R17") (pin "1") (pinfunction "1_1") (pintype "passive"))
      (node (ref "U2") (pin "1") (pinfunction "G_1") (pintype "passive"))
    )
    (net (code "45") (name "Net-(Q2-G)") (class "Default")
      (node (ref "Q2") (pin "1") (pinfunction "G_1") (pintype "passive"))
      (node (ref "R20") (pin "2") (pinfunction "2_2") (pintype "passive"))
      (node (ref "R22") (pin "2") (pinfunction "2_2") (pintype "passive"))
    )
    (net (code "46") (name "Net-(U4-ALERT)") (class "Default")
      (node (ref "R21") (pin "2") (pinfunction "2_2") (pintype "passive"))
      (node (ref "U4") (pin "13") (pinfunction "ALERT_13") (pintype "open_collector"))
    )
    (net (code "47") (name "Net-(U6A-Y)") (class "Default")
      (node (ref "R20") (pin "1") (pinfunction "1_1") (pintype "passive"))
      (node (ref "U6") (pin "4") (pinfunction "Y_4") (pintype "output"))
    )
    (net (code "48") (name "Pack+") (class "Default")
      (node (ref "R12") (pin "1") (pinfunction "1_1") (pintype "passive"))
      (node (ref "U1") (pin "1") (pinfunction "IN+_1") (pintype "passive"))
      (node (ref "U1") (pin "2") (pinfunction "IN+_2") (pintype "passive"))
    )
    (net (code "49") (name "Pack+ Out") (class "Default")
      (node (ref "U2") (pin "4") (pinfunction "D_4") (pintype "passive"))
    )
    (net (code "50") (name "Pack+ Sensor Out") (class "Default")
      (node (ref "R17") (pin "2") (pinfunction "2_2") (pintype "passive"))
      (node (ref "U1") (pin "3") (pinfunction "IN-_3") (pintype "passive"))
      (node (ref "U1") (pin "4") (pinfunction "IN-_4") (pintype "passive"))
      (node (ref "U2") (pin "3") (pinfunction "S_3") (pintype "passive"))
    )
    (net (code "51") (name "Pack-") (class "Default")
      (node (ref "R13") (pin "1") (pinfunction "1_1") (pintype "passive"))
      (node (ref "R19") (pin "2") (pinfunction "2_2") (pintype "passive"))
      (node (ref "R_sense") (pin "2") (pinfunction "2_2") (pintype "passive"))
    )
    (net (code "52") (name "unconnected-(D4-CH4-Pad5)") (class "Default")
      (node (ref "D4") (pin "5") (pinfunction "CH4_5") (pintype "passive+no_connect"))
    )
    (net (code "53") (name "unconnected-(D4-NC-Pad6)") (class "Default")
      (node (ref "D4") (pin "6") (pinfunction "NC_6") (pintype "passive+no_connect"))
    )
    (net (code "54") (name "unconnected-(D4-NC-Pad7)") (class "Default")
      (node (ref "D4") (pin "7") (pinfunction "NC_7") (pintype "passive+no_connect"))
    )
    (net (code "55") (name "unconnected-(D4-NC-Pad9)") (class "Default")
      (node (ref "D4") (pin "9") (pinfunction "NC_9") (pintype "passive+no_connect"))
    )
    (net (code "56") (name "unconnected-(D4-NC-Pad10)") (class "Default")
      (node (ref "D4") (pin "10") (pinfunction "NC_10") (pintype "passive+no_connect"))
    )
    (net (code "57") (name "unconnected-(J1-Pad8)") (class "Default")
      (node (ref "J1") (pin "8") (pinfunction "8_8") (pintype "passive"))
    )
    (net (code "58") (name "unconnected-(J2-Pad3)") (class "Default")
      (node (ref "J2") (pin "3") (pinfunction "3_3") (pintype "passive"))
    )
    (net (code "59") (name "unconnected-(J2-Pad5)") (class "Default")
      (node (ref "J2") (pin "5") (pinfunction "5_5") (pintype "passive"))
    )
    (net (code "60") (name "unconnected-(J2-Pad6)") (class "Default")
      (node (ref "J2") (pin "6") (pinfunction "6_6") (pintype "passive"))
    )
    (net (code "61") (name "unconnected-(J2-Pad8)") (class "Default")
      (node (ref "J2") (pin "8") (pinfunction "8_8") (pintype "passive"))
    )
    (net (code "62") (name "unconnected-(J2-Pad13)") (class "Default")
      (node (ref "J2") (pin "13") (pinfunction "13_13") (pintype "passive"))
    )
    (net (code "63") (name "unconnected-(J2-Pad14)") (class "Default")
      (node (ref "J2") (pin "14") (pinfunction "14_14") (pintype "passive"))
    )
    (net (code "64") (name "unconnected-(U1-NC-Pad6)") (class "Default")
      (node (ref "U1") (pin "6") (pinfunction "NC_6") (pintype "passive+no_connect"))
    )
    (net (code "65") (name "unconnected-(U3-PA8-Pad18)") (class "Default")
      (node (ref "U3") (pin "18") (pinfunction "PA8_18") (pintype "bidirectional"))
    )
    (net (code "66") (name "unconnected-(U3-PA12-Pad22)") (class "Default")
      (node (ref "U3") (pin "22") (pinfunction "PA12_22") (pintype "bidirectional"))
    )
    (net (code "67") (name "unconnected-(U3-PA15-Pad25)") (class "Default")
      (node (ref "U3") (pin "25") (pinfunction "PA15_25") (pintype "bidirectional"))
    )
    (net (code "68") (name "unconnected-(U3-PB3-Pad26)") (class "Default")
      (node (ref "U3") (pin "26") (pinfunction "PB3_26") (pintype "bidirectional"))
    )
    (net (code "69") (name "unconnected-(U3-PB4-Pad27)") (class "Default")
      (node (ref "U3") (pin "27") (pinfunction "PB4_27") (pintype "bidirectional"))
    )
    (net (code "70") (name "unconnected-(U3-PF1-OSC_OUT(PF1)-Pad3)") (class "Default")
      (node (ref "U3") (pin "3") (pinfunction "PF1-OSC_OUT(PF1)_3") (pintype "bidirectional"))
    )
    (net (code "71") (name "unconnected-(U6B-NC-Pad1)") (class "Default")
      (node (ref "U6") (pin "1") (pinfunction "NC_1") (pintype "passive+no_connect"))
    )
  )
)
